# EEZ_DIB_v1_0_backplane_dimensions.net
KiCad netlist of a schematic drawn in EAGLE
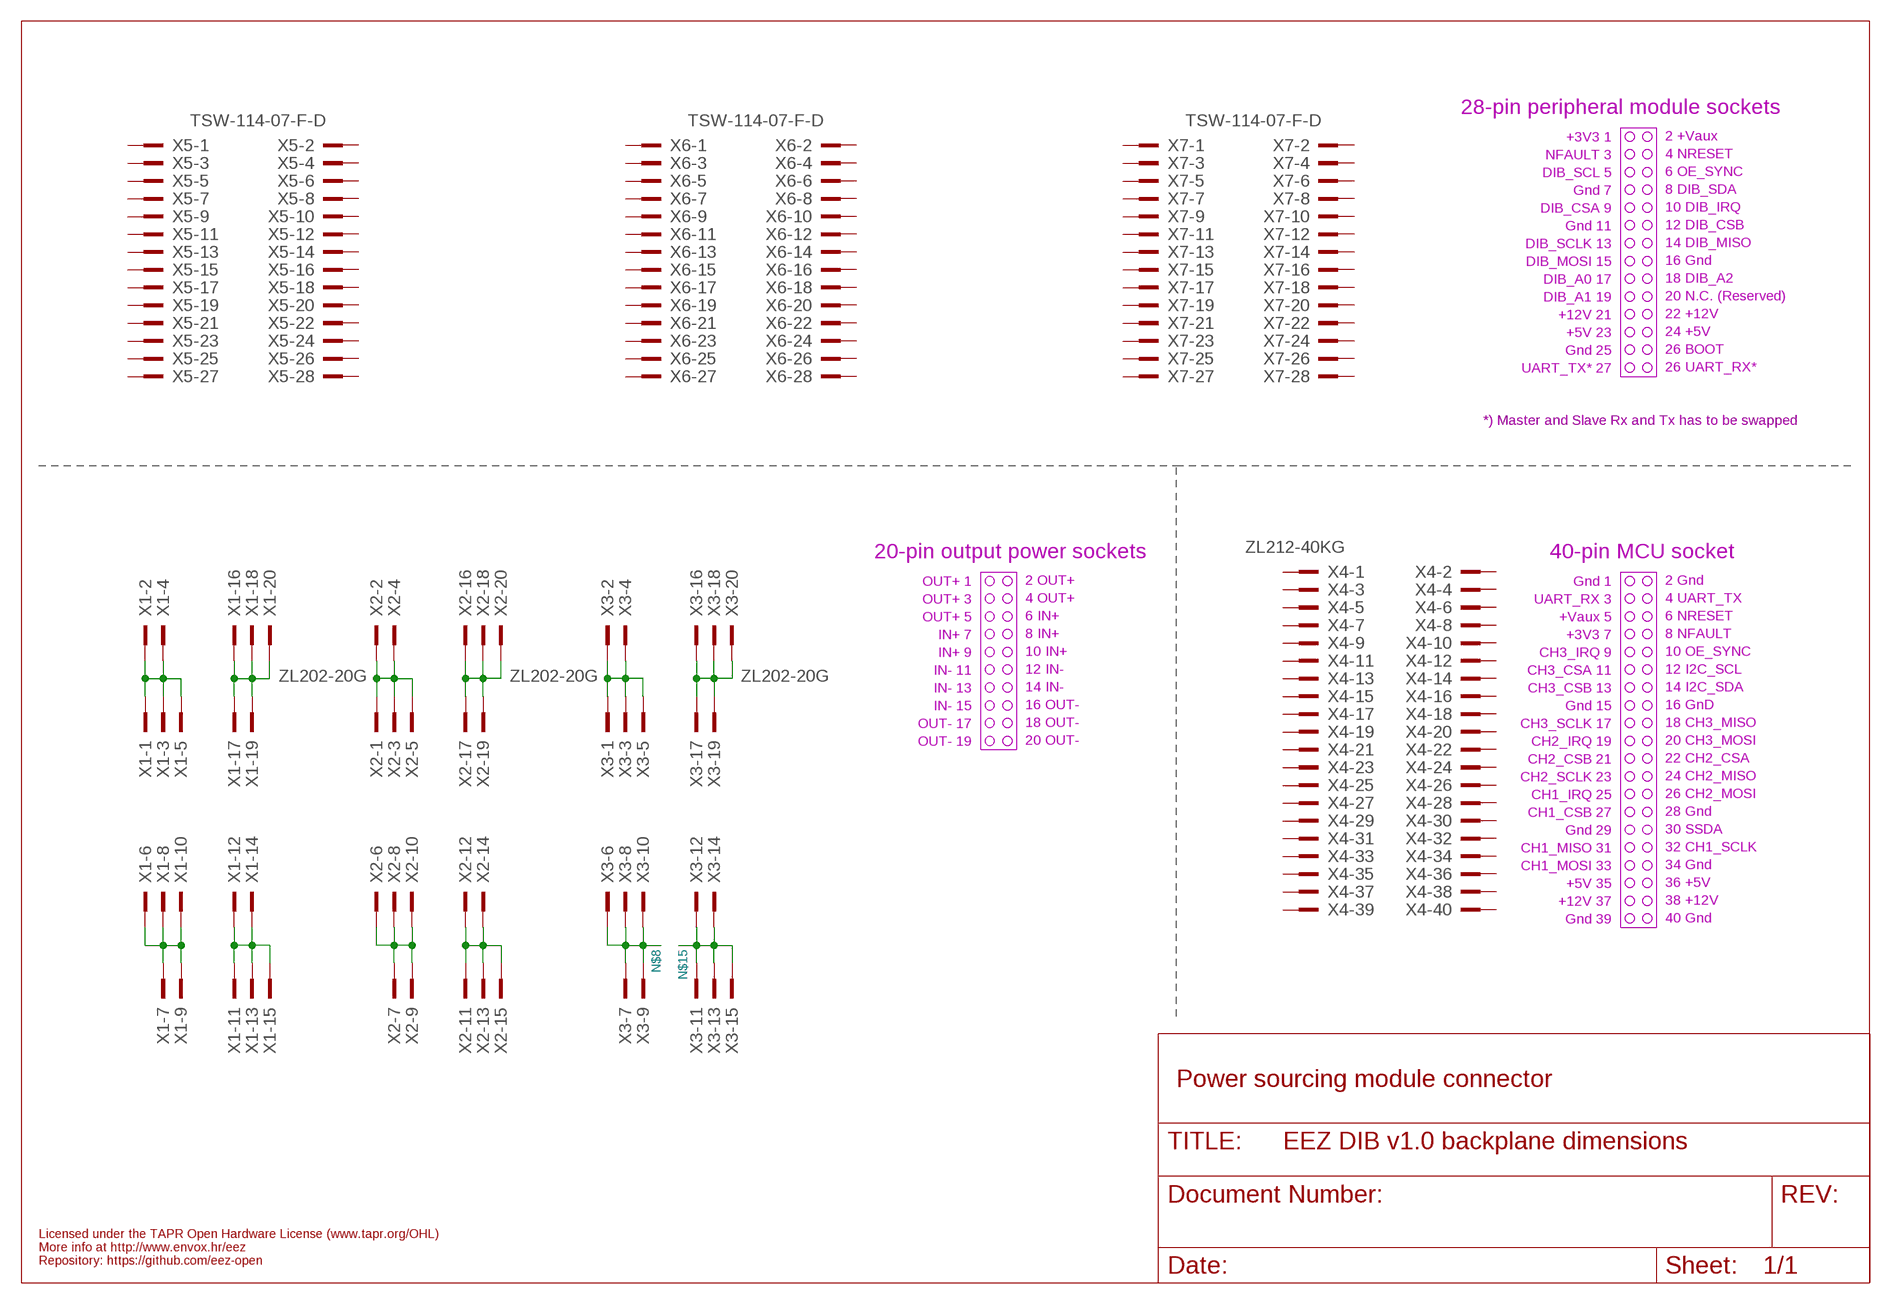
[diagram p0: schematic, sheet 1]

(export (version "E")
  (design (tool "Eeschema 10.0.6"))
  (components
    (comp (ref "X1")
      (value "ZL202-20G")
      (footprint "eagle-import:DS1021-2_10SF11")
      (libsource (lib "eagle-import") (part "DS1021-210SF11"))
    )
    (comp (ref "X2")
      (value "ZL202-20G")
      (footprint "eagle-import:DS1021-2_10SF11")
      (libsource (lib "eagle-import") (part "DS1021-210SF11"))
    )
    (comp (ref "X3")
      (value "ZL202-20G")
      (footprint "eagle-import:DS1021-2_10SF11")
      (libsource (lib "eagle-import") (part "DS1021-210SF11"))
    )
    (comp (ref "X4")
      (value "ZL212-40KG")
      (footprint "eagle-import:ZL212-40KG")
      (libsource (lib "eagle-import") (part "ZL212-40KG"))
    )
    (comp (ref "X5")
      (value "TSW-114-07-F-D")
      (footprint "eagle-import:TSW-114-07-F-D")
      (libsource (lib "eagle-import") (part "TSW-114-07-F-D"))
    )
    (comp (ref "X6")
      (value "TSW-114-07-F-D")
      (footprint "eagle-import:TSW-114-07-F-D")
      (libsource (lib "eagle-import") (part "TSW-114-07-F-D"))
    )
    (comp (ref "X7")
      (value "TSW-114-07-F-D")
      (footprint "eagle-import:TSW-114-07-F-D")
      (libsource (lib "eagle-import") (part "TSW-114-07-F-D"))
    )
  )
  (nets
    (net (code "1") (name "/N$8") (class "Default")
      (node (ref "X3") (pin "10") (pinfunction "1_10") (pintype "passive"))
      (node (ref "X3") (pin "6") (pinfunction "1_6") (pintype "passive"))
      (node (ref "X3") (pin "7") (pinfunction "1_7") (pintype "passive"))
      (node (ref "X3") (pin "8") (pinfunction "1_8") (pintype "passive"))
      (node (ref "X3") (pin "9") (pinfunction "1_9") (pintype "passive"))
    )
    (net (code "2") (name "/N$15") (class "Default")
      (node (ref "X3") (pin "11") (pinfunction "1_11") (pintype "passive"))
      (node (ref "X3") (pin "12") (pinfunction "1_12") (pintype "passive"))
      (node (ref "X3") (pin "13") (pinfunction "1_13") (pintype "passive"))
      (node (ref "X3") (pin "14") (pinfunction "1_14") (pintype "passive"))
      (node (ref "X3") (pin "15") (pinfunction "1_15") (pintype "passive"))
    )
    (net (code "3") (name "Net-(X1B-1)") (class "Default")
      (node (ref "X1") (pin "10") (pinfunction "1_10") (pintype "passive"))
      (node (ref "X1") (pin "6") (pinfunction "1_6") (pintype "passive"))
      (node (ref "X1") (pin "7") (pinfunction "1_7") (pintype "passive"))
      (node (ref "X1") (pin "8") (pinfunction "1_8") (pintype "passive"))
      (node (ref "X1") (pin "9") (pinfunction "1_9") (pintype "passive"))
    )
    (net (code "4") (name "Net-(X1C-1)") (class "Default")
      (node (ref "X1") (pin "11") (pinfunction "1_11") (pintype "passive"))
      (node (ref "X1") (pin "12") (pinfunction "1_12") (pintype "passive"))
      (node (ref "X1") (pin "13") (pinfunction "1_13") (pintype "passive"))
      (node (ref "X1") (pin "14") (pinfunction "1_14") (pintype "passive"))
      (node (ref "X1") (pin "15") (pinfunction "1_15") (pintype "passive"))
    )
    (net (code "5") (name "Net-(X1H-1)") (class "Default")
      (node (ref "X1") (pin "16") (pinfunction "1_16") (pintype "passive"))
      (node (ref "X1") (pin "17") (pinfunction "1_17") (pintype "passive"))
      (node (ref "X1") (pin "18") (pinfunction "1_18") (pintype "passive"))
      (node (ref "X1") (pin "19") (pinfunction "1_19") (pintype "passive"))
      (node (ref "X1") (pin "20") (pinfunction "1_20") (pintype "passive"))
    )
    (net (code "6") (name "Net-(X1L-1)") (class "Default")
      (node (ref "X1") (pin "1") (pinfunction "1_1") (pintype "passive"))
      (node (ref "X1") (pin "2") (pinfunction "1_2") (pintype "passive"))
      (node (ref "X1") (pin "3") (pinfunction "1_3") (pintype "passive"))
      (node (ref "X1") (pin "4") (pinfunction "1_4") (pintype "passive"))
      (node (ref "X1") (pin "5") (pinfunction "1_5") (pintype "passive"))
    )
    (net (code "7") (name "Net-(X2B-1)") (class "Default")
      (node (ref "X2") (pin "10") (pinfunction "1_10") (pintype "passive"))
      (node (ref "X2") (pin "6") (pinfunction "1_6") (pintype "passive"))
      (node (ref "X2") (pin "7") (pinfunction "1_7") (pintype "passive"))
      (node (ref "X2") (pin "8") (pinfunction "1_8") (pintype "passive"))
      (node (ref "X2") (pin "9") (pinfunction "1_9") (pintype "passive"))
    )
    (net (code "8") (name "Net-(X2C-1)") (class "Default")
      (node (ref "X2") (pin "11") (pinfunction "1_11") (pintype "passive"))
      (node (ref "X2") (pin "12") (pinfunction "1_12") (pintype "passive"))
      (node (ref "X2") (pin "13") (pinfunction "1_13") (pintype "passive"))
      (node (ref "X2") (pin "14") (pinfunction "1_14") (pintype "passive"))
      (node (ref "X2") (pin "15") (pinfunction "1_15") (pintype "passive"))
    )
    (net (code "9") (name "Net-(X2H-1)") (class "Default")
      (node (ref "X2") (pin "16") (pinfunction "1_16") (pintype "passive"))
      (node (ref "X2") (pin "17") (pinfunction "1_17") (pintype "passive"))
      (node (ref "X2") (pin "18") (pinfunction "1_18") (pintype "passive"))
      (node (ref "X2") (pin "19") (pinfunction "1_19") (pintype "passive"))
      (node (ref "X2") (pin "20") (pinfunction "1_20") (pintype "passive"))
    )
    (net (code "10") (name "Net-(X2L-1)") (class "Default")
      (node (ref "X2") (pin "1") (pinfunction "1_1") (pintype "passive"))
      (node (ref "X2") (pin "2") (pinfunction "1_2") (pintype "passive"))
      (node (ref "X2") (pin "3") (pinfunction "1_3") (pintype "passive"))
      (node (ref "X2") (pin "4") (pinfunction "1_4") (pintype "passive"))
      (node (ref "X2") (pin "5") (pinfunction "1_5") (pintype "passive"))
    )
    (net (code "11") (name "Net-(X3H-1)") (class "Default")
      (node (ref "X3") (pin "16") (pinfunction "1_16") (pintype "passive"))
      (node (ref "X3") (pin "17") (pinfunction "1_17") (pintype "passive"))
      (node (ref "X3") (pin "18") (pinfunction "1_18") (pintype "passive"))
      (node (ref "X3") (pin "19") (pinfunction "1_19") (pintype "passive"))
      (node (ref "X3") (pin "20") (pinfunction "1_20") (pintype "passive"))
    )
    (net (code "12") (name "Net-(X3L-1)") (class "Default")
      (node (ref "X3") (pin "1") (pinfunction "1_1") (pintype "passive"))
      (node (ref "X3") (pin "2") (pinfunction "1_2") (pintype "passive"))
      (node (ref "X3") (pin "3") (pinfunction "1_3") (pintype "passive"))
      (node (ref "X3") (pin "4") (pinfunction "1_4") (pintype "passive"))
      (node (ref "X3") (pin "5") (pinfunction "1_5") (pintype "passive"))
    )
    (net (code "13") (name "unconnected-(X4-Pad1)") (class "Default")
      (node (ref "X4") (pin "1") (pinfunction "1_1") (pintype "passive"))
    )
    (net (code "14") (name "unconnected-(X4AA-1-Pad33)") (class "Default")
      (node (ref "X4") (pin "33") (pinfunction "1_33") (pintype "passive"))
    )
    (net (code "15") (name "unconnected-(X4AB-1-Pad34)") (class "Default")
      (node (ref "X4") (pin "34") (pinfunction "1_34") (pintype "passive"))
    )
    (net (code "16") (name "unconnected-(X4AC-1-Pad35)") (class "Default")
      (node (ref "X4") (pin "35") (pinfunction "1_35") (pintype "passive"))
    )
    (net (code "17") (name "unconnected-(X4AD-1-Pad36)") (class "Default")
      (node (ref "X4") (pin "36") (pinfunction "1_36") (pintype "passive"))
    )
    (net (code "18") (name "unconnected-(X4AE-1-Pad37)") (class "Default")
      (node (ref "X4") (pin "37") (pinfunction "1_37") (pintype "passive"))
    )
    (net (code "19") (name "unconnected-(X4AF-1-Pad38)") (class "Default")
      (node (ref "X4") (pin "38") (pinfunction "1_38") (pintype "passive"))
    )
    (net (code "20") (name "unconnected-(X4AG-1-Pad39)") (class "Default")
      (node (ref "X4") (pin "39") (pinfunction "1_39") (pintype "passive"))
    )
    (net (code "21") (name "unconnected-(X4AH-1-Pad4)") (class "Default")
      (node (ref "X4") (pin "4") (pinfunction "1_4") (pintype "passive"))
    )
    (net (code "22") (name "unconnected-(X4AI-1-Pad40)") (class "Default")
      (node (ref "X4") (pin "40") (pinfunction "1_40") (pintype "passive"))
    )
    (net (code "23") (name "unconnected-(X4AJ-1-Pad5)") (class "Default")
      (node (ref "X4") (pin "5") (pinfunction "1_5") (pintype "passive"))
    )
    (net (code "24") (name "unconnected-(X4AK-1-Pad6)") (class "Default")
      (node (ref "X4") (pin "6") (pinfunction "1_6") (pintype "passive"))
    )
    (net (code "25") (name "unconnected-(X4AL-1-Pad7)") (class "Default")
      (node (ref "X4") (pin "7") (pinfunction "1_7") (pintype "passive"))
    )
    (net (code "26") (name "unconnected-(X4AM-1-Pad8)") (class "Default")
      (node (ref "X4") (pin "8") (pinfunction "1_8") (pintype "passive"))
    )
    (net (code "27") (name "unconnected-(X4AN-1-Pad9)") (class "Default")
      (node (ref "X4") (pin "9") (pinfunction "1_9") (pintype "passive"))
    )
    (net (code "28") (name "unconnected-(X4B-1-Pad10)") (class "Default")
      (node (ref "X4") (pin "10") (pinfunction "1_10") (pintype "passive"))
    )
    (net (code "29") (name "unconnected-(X4C-1-Pad11)") (class "Default")
      (node (ref "X4") (pin "11") (pinfunction "1_11") (pintype "passive"))
    )
    (net (code "30") (name "unconnected-(X4D-1-Pad12)") (class "Default")
      (node (ref "X4") (pin "12") (pinfunction "1_12") (pintype "passive"))
    )
    (net (code "31") (name "unconnected-(X4E-1-Pad13)") (class "Default")
      (node (ref "X4") (pin "13") (pinfunction "1_13") (pintype "passive"))
    )
    (net (code "32") (name "unconnected-(X4F-1-Pad14)") (class "Default")
      (node (ref "X4") (pin "14") (pinfunction "1_14") (pintype "passive"))
    )
    (net (code "33") (name "unconnected-(X4G-1-Pad15)") (class "Default")
      (node (ref "X4") (pin "15") (pinfunction "1_15") (pintype "passive"))
    )
    (net (code "34") (name "unconnected-(X4H-1-Pad16)") (class "Default")
      (node (ref "X4") (pin "16") (pinfunction "1_16") (pintype "passive"))
    )
    (net (code "35") (name "unconnected-(X4I-1-Pad17)") (class "Default")
      (node (ref "X4") (pin "17") (pinfunction "1_17") (pintype "passive"))
    )
    (net (code "36") (name "unconnected-(X4J-1-Pad18)") (class "Default")
      (node (ref "X4") (pin "18") (pinfunction "1_18") (pintype "passive"))
    )
    (net (code "37") (name "unconnected-(X4K-1-Pad19)") (class "Default")
      (node (ref "X4") (pin "19") (pinfunction "1_19") (pintype "passive"))
    )
    (net (code "38") (name "unconnected-(X4L-1-Pad2)") (class "Default")
      (node (ref "X4") (pin "2") (pinfunction "1_2") (pintype "passive"))
    )
    (net (code "39") (name "unconnected-(X4M-1-Pad20)") (class "Default")
      (node (ref "X4") (pin "20") (pinfunction "1_20") (pintype "passive"))
    )
    (net (code "40") (name "unconnected-(X4N-1-Pad21)") (class "Default")
      (node (ref "X4") (pin "21") (pinfunction "1_21") (pintype "passive"))
    )
    (net (code "41") (name "unconnected-(X4O-1-Pad22)") (class "Default")
      (node (ref "X4") (pin "22") (pinfunction "1_22") (pintype "passive"))
    )
    (net (code "42") (name "unconnected-(X4P-1-Pad23)") (class "Default")
      (node (ref "X4") (pin "23") (pinfunction "1_23") (pintype "passive"))
    )
    (net (code "43") (name "unconnected-(X4Q-1-Pad24)") (class "Default")
      (node (ref "X4") (pin "24") (pinfunction "1_24") (pintype "passive"))
    )
    (net (code "44") (name "unconnected-(X4R-1-Pad25)") (class "Default")
      (node (ref "X4") (pin "25") (pinfunction "1_25") (pintype "passive"))
    )
    (net (code "45") (name "unconnected-(X4S-1-Pad26)") (class "Default")
      (node (ref "X4") (pin "26") (pinfunction "1_26") (pintype "passive"))
    )
    (net (code "46") (name "unconnected-(X4T-1-Pad27)") (class "Default")
      (node (ref "X4") (pin "27") (pinfunction "1_27") (pintype "passive"))
    )
    (net (code "47") (name "unconnected-(X4U-1-Pad28)") (class "Default")
      (node (ref "X4") (pin "28") (pinfunction "1_28") (pintype "passive"))
    )
    (net (code "48") (name "unconnected-(X4V-1-Pad29)") (class "Default")
      (node (ref "X4") (pin "29") (pinfunction "1_29") (pintype "passive"))
    )
    (net (code "49") (name "unconnected-(X4W-1-Pad3)") (class "Default")
      (node (ref "X4") (pin "3") (pinfunction "1_3") (pintype "passive"))
    )
    (net (code "50") (name "unconnected-(X4X-1-Pad30)") (class "Default")
      (node (ref "X4") (pin "30") (pinfunction "1_30") (pintype "passive"))
    )
    (net (code "51") (name "unconnected-(X4Y-1-Pad31)") (class "Default")
      (node (ref "X4") (pin "31") (pinfunction "1_31") (pintype "passive"))
    )
    (net (code "52") (name "unconnected-(X4Z-1-Pad32)") (class "Default")
      (node (ref "X4") (pin "32") (pinfunction "1_32") (pintype "passive"))
    )
    (net (code "53") (name "unconnected-(X5-Pad1)") (class "Default")
      (node (ref "X5") (pin "1") (pinfunction "1_1") (pintype "passive"))
    )
    (net (code "54") (name "unconnected-(X5AA-1-Pad8)") (class "Default")
      (node (ref "X5") (pin "8") (pinfunction "1_8") (pintype "passive"))
    )
    (net (code "55") (name "unconnected-(X5AB-1-Pad9)") (class "Default")
      (node (ref "X5") (pin "9") (pinfunction "1_9") (pintype "passive"))
    )
    (net (code "56") (name "unconnected-(X5B-1-Pad10)") (class "Default")
      (node (ref "X5") (pin "10") (pinfunction "1_10") (pintype "passive"))
    )
    (net (code "57") (name "unconnected-(X5C-1-Pad11)") (class "Default")
      (node (ref "X5") (pin "11") (pinfunction "1_11") (pintype "passive"))
    )
    (net (code "58") (name "unconnected-(X5D-1-Pad12)") (class "Default")
      (node (ref "X5") (pin "12") (pinfunction "1_12") (pintype "passive"))
    )
    (net (code "59") (name "unconnected-(X5E-1-Pad13)") (class "Default")
      (node (ref "X5") (pin "13") (pinfunction "1_13") (pintype "passive"))
    )
    (net (code "60") (name "unconnected-(X5F-1-Pad14)") (class "Default")
      (node (ref "X5") (pin "14") (pinfunction "1_14") (pintype "passive"))
    )
    (net (code "61") (name "unconnected-(X5G-1-Pad15)") (class "Default")
      (node (ref "X5") (pin "15") (pinfunction "1_15") (pintype "passive"))
    )
    (net (code "62") (name "unconnected-(X5H-1-Pad16)") (class "Default")
      (node (ref "X5") (pin "16") (pinfunction "1_16") (pintype "passive"))
    )
    (net (code "63") (name "unconnected-(X5I-1-Pad17)") (class "Default")
      (node (ref "X5") (pin "17") (pinfunction "1_17") (pintype "passive"))
    )
    (net (code "64") (name "unconnected-(X5J-1-Pad18)") (class "Default")
      (node (ref "X5") (pin "18") (pinfunction "1_18") (pintype "passive"))
    )
    (net (code "65") (name "unconnected-(X5K-1-Pad19)") (class "Default")
      (node (ref "X5") (pin "19") (pinfunction "1_19") (pintype "passive"))
    )
    (net (code "66") (name "unconnected-(X5L-1-Pad2)") (class "Default")
      (node (ref "X5") (pin "2") (pinfunction "1_2") (pintype "passive"))
    )
    (net (code "67") (name "unconnected-(X5M-1-Pad20)") (class "Default")
      (node (ref "X5") (pin "20") (pinfunction "1_20") (pintype "passive"))
    )
    (net (code "68") (name "unconnected-(X5N-1-Pad21)") (class "Default")
      (node (ref "X5") (pin "21") (pinfunction "1_21") (pintype "passive"))
    )
    (net (code "69") (name "unconnected-(X5O-1-Pad22)") (class "Default")
      (node (ref "X5") (pin "22") (pinfunction "1_22") (pintype "passive"))
    )
    (net (code "70") (name "unconnected-(X5P-1-Pad23)") (class "Default")
      (node (ref "X5") (pin "23") (pinfunction "1_23") (pintype "passive"))
    )
    (net (code "71") (name "unconnected-(X5Q-1-Pad24)") (class "Default")
      (node (ref "X5") (pin "24") (pinfunction "1_24") (pintype "passive"))
    )
    (net (code "72") (name "unconnected-(X5R-1-Pad25)") (class "Default")
      (node (ref "X5") (pin "25") (pinfunction "1_25") (pintype "passive"))
    )
    (net (code "73") (name "unconnected-(X5S-1-Pad26)") (class "Default")
      (node (ref "X5") (pin "26") (pinfunction "1_26") (pintype "passive"))
    )
    (net (code "74") (name "unconnected-(X5T-1-Pad27)") (class "Default")
      (node (ref "X5") (pin "27") (pinfunction "1_27") (pintype "passive"))
    )
    (net (code "75") (name "unconnected-(X5U-1-Pad28)") (class "Default")
      (node (ref "X5") (pin "28") (pinfunction "1_28") (pintype "passive"))
    )
    (net (code "76") (name "unconnected-(X5V-1-Pad3)") (class "Default")
      (node (ref "X5") (pin "3") (pinfunction "1_3") (pintype "passive"))
    )
    (net (code "77") (name "unconnected-(X5W-1-Pad4)") (class "Default")
      (node (ref "X5") (pin "4") (pinfunction "1_4") (pintype "passive"))
    )
    (net (code "78") (name "unconnected-(X5X-1-Pad5)") (class "Default")
      (node (ref "X5") (pin "5") (pinfunction "1_5") (pintype "passive"))
    )
    (net (code "79") (name "unconnected-(X5Y-1-Pad6)") (class "Default")
      (node (ref "X5") (pin "6") (pinfunction "1_6") (pintype "passive"))
    )
    (net (code "80") (name "unconnected-(X5Z-1-Pad7)") (class "Default")
      (node (ref "X5") (pin "7") (pinfunction "1_7") (pintype "passive"))
    )
    (net (code "81") (name "unconnected-(X6-Pad1)") (class "Default")
      (node (ref "X6") (pin "1") (pinfunction "1_1") (pintype "passive"))
    )
    (net (code "82") (name "unconnected-(X6AA-1-Pad8)") (class "Default")
      (node (ref "X6") (pin "8") (pinfunction "1_8") (pintype "passive"))
    )
    (net (code "83") (name "unconnected-(X6AB-1-Pad9)") (class "Default")
      (node (ref "X6") (pin "9") (pinfunction "1_9") (pintype "passive"))
    )
    (net (code "84") (name "unconnected-(X6B-1-Pad10)") (class "Default")
      (node (ref "X6") (pin "10") (pinfunction "1_10") (pintype "passive"))
    )
    (net (code "85") (name "unconnected-(X6C-1-Pad11)") (class "Default")
      (node (ref "X6") (pin "11") (pinfunction "1_11") (pintype "passive"))
    )
    (net (code "86") (name "unconnected-(X6D-1-Pad12)") (class "Default")
      (node (ref "X6") (pin "12") (pinfunction "1_12") (pintype "passive"))
    )
    (net (code "87") (name "unconnected-(X6E-1-Pad13)") (class "Default")
      (node (ref "X6") (pin "13") (pinfunction "1_13") (pintype "passive"))
    )
    (net (code "88") (name "unconnected-(X6F-1-Pad14)") (class "Default")
      (node (ref "X6") (pin "14") (pinfunction "1_14") (pintype "passive"))
    )
    (net (code "89") (name "unconnected-(X6G-1-Pad15)") (class "Default")
      (node (ref "X6") (pin "15") (pinfunction "1_15") (pintype "passive"))
    )
    (net (code "90") (name "unconnected-(X6H-1-Pad16)") (class "Default")
      (node (ref "X6") (pin "16") (pinfunction "1_16") (pintype "passive"))
    )
    (net (code "91") (name "unconnected-(X6I-1-Pad17)") (class "Default")
      (node (ref "X6") (pin "17") (pinfunction "1_17") (pintype "passive"))
    )
    (net (code "92") (name "unconnected-(X6J-1-Pad18)") (class "Default")
      (node (ref "X6") (pin "18") (pinfunction "1_18") (pintype "passive"))
    )
    (net (code "93") (name "unconnected-(X6K-1-Pad19)") (class "Default")
      (node (ref "X6") (pin "19") (pinfunction "1_19") (pintype "passive"))
    )
    (net (code "94") (name "unconnected-(X6L-1-Pad2)") (class "Default")
      (node (ref "X6") (pin "2") (pinfunction "1_2") (pintype "passive"))
    )
    (net (code "95") (name "unconnected-(X6M-1-Pad20)") (class "Default")
      (node (ref "X6") (pin "20") (pinfunction "1_20") (pintype "passive"))
    )
    (net (code "96") (name "unconnected-(X6N-1-Pad21)") (class "Default")
      (node (ref "X6") (pin "21") (pinfunction "1_21") (pintype "passive"))
    )
    (net (code "97") (name "unconnected-(X6O-1-Pad22)") (class "Default")
      (node (ref "X6") (pin "22") (pinfunction "1_22") (pintype "passive"))
    )
    (net (code "98") (name "unconnected-(X6P-1-Pad23)") (class "Default")
      (node (ref "X6") (pin "23") (pinfunction "1_23") (pintype "passive"))
    )
    (net (code "99") (name "unconnected-(X6Q-1-Pad24)") (class "Default")
      (node (ref "X6") (pin "24") (pinfunction "1_24") (pintype "passive"))
    )
    (net (code "100") (name "unconnected-(X6R-1-Pad25)") (class "Default")
      (node (ref "X6") (pin "25") (pinfunction "1_25") (pintype "passive"))
    )
    (net (code "101") (name "unconnected-(X6S-1-Pad26)") (class "Default")
      (node (ref "X6") (pin "26") (pinfunction "1_26") (pintype "passive"))
    )
    (net (code "102") (name "unconnected-(X6T-1-Pad27)") (class "Default")
      (node (ref "X6") (pin "27") (pinfunction "1_27") (pintype "passive"))
    )
    (net (code "103") (name "unconnected-(X6U-1-Pad28)") (class "Default")
      (node (ref "X6") (pin "28") (pinfunction "1_28") (pintype "passive"))
    )
    (net (code "104") (name "unconnected-(X6V-1-Pad3)") (class "Default")
      (node (ref "X6") (pin "3") (pinfunction "1_3") (pintype "passive"))
    )
    (net (code "105") (name "unconnected-(X6W-1-Pad4)") (class "Default")
      (node (ref "X6") (pin "4") (pinfunction "1_4") (pintype "passive"))
    )
    (net (code "106") (name "unconnected-(X6X-1-Pad5)") (class "Default")
      (node (ref "X6") (pin "5") (pinfunction "1_5") (pintype "passive"))
    )
    (net (code "107") (name "unconnected-(X6Y-1-Pad6)") (class "Default")
      (node (ref "X6") (pin "6") (pinfunction "1_6") (pintype "passive"))
    )
    (net (code "108") (name "unconnected-(X6Z-1-Pad7)") (class "Default")
      (node (ref "X6") (pin "7") (pinfunction "1_7") (pintype "passive"))
    )
    (net (code "109") (name "unconnected-(X7-Pad1)") (class "Default")
      (node (ref "X7") (pin "1") (pinfunction "1_1") (pintype "passive"))
    )
    (net (code "110") (name "unconnected-(X7AA-1-Pad8)") (class "Default")
      (node (ref "X7") (pin "8") (pinfunction "1_8") (pintype "passive"))
    )
    (net (code "111") (name "unconnected-(X7AB-1-Pad9)") (class "Default")
      (node (ref "X7") (pin "9") (pinfunction "1_9") (pintype "passive"))
    )
    (net (code "112") (name "unconnected-(X7B-1-Pad10)") (class "Default")
      (node (ref "X7") (pin "10") (pinfunction "1_10") (pintype "passive"))
    )
    (net (code "113") (name "unconnected-(X7C-1-Pad11)") (class "Default")
      (node (ref "X7") (pin "11") (pinfunction "1_11") (pintype "passive"))
    )
    (net (code "114") (name "unconnected-(X7D-1-Pad12)") (class "Default")
      (node (ref "X7") (pin "12") (pinfunction "1_12") (pintype "passive"))
    )
    (net (code "115") (name "unconnected-(X7E-1-Pad13)") (class "Default")
      (node (ref "X7") (pin "13") (pinfunction "1_13") (pintype "passive"))
    )
    (net (code "116") (name "unconnected-(X7F-1-Pad14)") (class "Default")
      (node (ref "X7") (pin "14") (pinfunction "1_14") (pintype "passive"))
    )
    (net (code "117") (name "unconnected-(X7G-1-Pad15)") (class "Default")
      (node (ref "X7") (pin "15") (pinfunction "1_15") (pintype "passive"))
    )
    (net (code "118") (name "unconnected-(X7H-1-Pad16)") (class "Default")
      (node (ref "X7") (pin "16") (pinfunction "1_16") (pintype "passive"))
    )
    (net (code "119") (name "unconnected-(X7I-1-Pad17)") (class "Default")
      (node (ref "X7") (pin "17") (pinfunction "1_17") (pintype "passive"))
    )
    (net (code "120") (name "unconnected-(X7J-1-Pad18)") (class "Default")
      (node (ref "X7") (pin "18") (pinfunction "1_18") (pintype "passive"))
    )
    (net (code "121") (name "unconnected-(X7K-1-Pad19)") (class "Default")
      (node (ref "X7") (pin "19") (pinfunction "1_19") (pintype "passive"))
    )
    (net (code "122") (name "unconnected-(X7L-1-Pad2)") (class "Default")
      (node (ref "X7") (pin "2") (pinfunction "1_2") (pintype "passive"))
    )
    (net (code "123") (name "unconnected-(X7M-1-Pad20)") (class "Default")
      (node (ref "X7") (pin "20") (pinfunction "1_20") (pintype "passive"))
    )
    (net (code "124") (name "unconnected-(X7N-1-Pad21)") (class "Default")
      (node (ref "X7") (pin "21") (pinfunction "1_21") (pintype "passive"))
    )
    (net (code "125") (name "unconnected-(X7O-1-Pad22)") (class "Default")
      (node (ref "X7") (pin "22") (pinfunction "1_22") (pintype "passive"))
    )
    (net (code "126") (name "unconnected-(X7P-1-Pad23)") (class "Default")
      (node (ref "X7") (pin "23") (pinfunction "1_23") (pintype "passive"))
    )
    (net (code "127") (name "unconnected-(X7Q-1-Pad24)") (class "Default")
      (node (ref "X7") (pin "24") (pinfunction "1_24") (pintype "passive"))
    )
    (net (code "128") (name "unconnected-(X7R-1-Pad25)") (class "Default")
      (node (ref "X7") (pin "25") (pinfunction "1_25") (pintype "passive"))
    )
    (net (code "129") (name "unconnected-(X7S-1-Pad26)") (class "Default")
      (node (ref "X7") (pin "26") (pinfunction "1_26") (pintype "passive"))
    )
    (net (code "130") (name "unconnected-(X7T-1-Pad27)") (class "Default")
      (node (ref "X7") (pin "27") (pinfunction "1_27") (pintype "passive"))
    )
    (net (code "131") (name "unconnected-(X7U-1-Pad28)") (class "Default")
      (node (ref "X7") (pin "28") (pinfunction "1_28") (pintype "passive"))
    )
    (net (code "132") (name "unconnected-(X7V-1-Pad3)") (class "Default")
      (node (ref "X7") (pin "3") (pinfunction "1_3") (pintype "passive"))
    )
    (net (code "133") (name "unconnected-(X7W-1-Pad4)") (class "Default")
      (node (ref "X7") (pin "4") (pinfunction "1_4") (pintype "passive"))
    )
    (net (code "134") (name "unconnected-(X7X-1-Pad5)") (class "Default")
      (node (ref "X7") (pin "5") (pinfunction "1_5") (pintype "passive"))
    )
    (net (code "135") (name "unconnected-(X7Y-1-Pad6)") (class "Default")
      (node (ref "X7") (pin "6") (pinfunction "1_6") (pintype "passive"))
    )
    (net (code "136") (name "unconnected-(X7Z-1-Pad7)") (class "Default")
      (node (ref "X7") (pin "7") (pinfunction "1_7") (pintype "passive"))
    )
  )
)
